# tb6612fng.net
KiCad netlist of a schematic drawn in Altium Designer
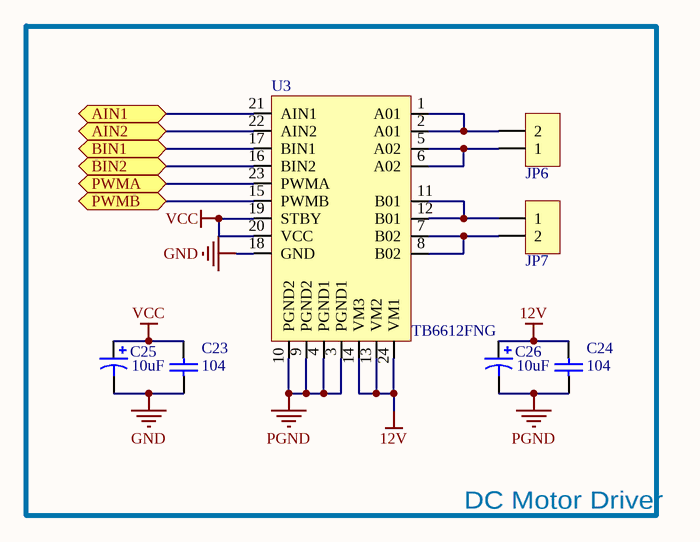
[diagram p0: tb6612fng.SchDoc]

(export (version "E")
  (design (tool "Eeschema 10.0.6"))
  (components
    (comp (ref "C23")
      (value "104")
      (footprint "C 0603_L")
      (description "Capacitor")
      (fields (field (name "PUBLISHER") "Altium Limited"))
      (libsource (lib "Miscellaneous Devices") (part "Cap"))
    )
    (comp (ref "C24")
      (value "104")
      (footprint "C 0603_L")
      (description "Capacitor")
      (fields (field (name "PUBLISHER") "Altium Limited"))
      (libsource (lib "Miscellaneous Devices") (part "Cap"))
    )
    (comp (ref "C25")
      (value "10uF")
      (footprint "CD A(3216)")
      (description "Polarized Capacitor (Radial)")
      (fields (field (name "PUBLISHER") "Altium Limited"))
      (libsource (lib "Miscellaneous Devices") (part "Cap Pol1"))
    )
    (comp (ref "C26")
      (value "10uF")
      (footprint "CD A(3216)")
      (description "Polarized Capacitor (Radial)")
      (fields (field (name "PUBLISHER") "Altium Limited"))
      (libsource (lib "Miscellaneous Devices") (part "Cap Pol1"))
    )
    (comp (ref "JP6")
      (value "HDR-1X2")
      (footprint "XH2.54-LI-2P")
      (description "2P接插件")
      (fields (field (name "版权归属") "源创客"))
      (libsource (lib "4.5   - 接插件-脚距2.54") (part "Header 2"))
    )
    (comp (ref "JP7")
      (value "HDR-1X2")
      (footprint "XH2.54-LI-2P")
      (description "2P接插件")
      (fields (field (name "版权归属") "源创客"))
      (libsource (lib "") (part "Header 2_1"))
    )
    (comp (ref "U3")
      (value "TB6612FNG")
      (footprint "SSOP24_N")
      (description "DC_MOTOR_DRIVER")
      (libsource (lib "主控板载芯片") (part "TB6612FNG"))
    )
  )
  (nets
    (net (code "1") (name "/AIN1") (class "Default")
      (node (ref "U3") (pin "21") (pinfunction "AIN1_21") (pintype "passive"))
    )
    (net (code "2") (name "/AIN2") (class "Default")
      (node (ref "U3") (pin "22") (pinfunction "AIN2_22") (pintype "passive"))
    )
    (net (code "3") (name "/BIN1") (class "Default")
      (node (ref "U3") (pin "17") (pinfunction "BIN1_17") (pintype "passive"))
    )
    (net (code "4") (name "/BIN2") (class "Default")
      (node (ref "U3") (pin "16") (pinfunction "BIN2_16") (pintype "passive"))
    )
    (net (code "5") (name "/PWMA") (class "Default")
      (node (ref "U3") (pin "23") (pinfunction "PWMA_23") (pintype "passive"))
    )
    (net (code "6") (name "/PWMB") (class "Default")
      (node (ref "U3") (pin "15") (pinfunction "PWMB_15") (pintype "passive"))
    )
    (net (code "7") (name "12V") (class "Default")
      (node (ref "C24") (pin "2") (pinfunction "2_2") (pintype "passive"))
      (node (ref "C26") (pin "1") (pinfunction "1_1") (pintype "passive"))
      (node (ref "U3") (pin "13") (pinfunction "VM2_13") (pintype "passive"))
      (node (ref "U3") (pin "14") (pinfunction "VM3_14") (pintype "passive"))
      (node (ref "U3") (pin "24") (pinfunction "VM1_24") (pintype "passive"))
    )
    (net (code "8") (name "GND") (class "Default")
      (node (ref "C23") (pin "1") (pinfunction "1_1") (pintype "passive"))
      (node (ref "C25") (pin "2") (pinfunction "2_2") (pintype "passive"))
      (node (ref "U3") (pin "18") (pinfunction "GND_18") (pintype "passive"))
    )
    (net (code "9") (name "Net-(JP6-Pad1)") (class "Default")
      (node (ref "JP6") (pin "1") (pinfunction "1_1") (pintype "passive"))
      (node (ref "U3") (pin "5") (pinfunction "A02_5") (pintype "passive"))
      (node (ref "U3") (pin "6") (pinfunction "A02_6") (pintype "passive"))
    )
    (net (code "10") (name "Net-(JP6-Pad2)") (class "Default")
      (node (ref "JP6") (pin "2") (pinfunction "2_2") (pintype "passive"))
      (node (ref "U3") (pin "1") (pinfunction "A01_1") (pintype "passive"))
      (node (ref "U3") (pin "2") (pinfunction "A01_2") (pintype "passive"))
    )
    (net (code "11") (name "Net-(JP7-Pad1)") (class "Default")
      (node (ref "JP7") (pin "1") (pinfunction "1_1") (pintype "passive"))
      (node (ref "U3") (pin "11") (pinfunction "B01_11") (pintype "passive"))
      (node (ref "U3") (pin "12") (pinfunction "B01_12") (pintype "passive"))
    )
    (net (code "12") (name "Net-(JP7-Pad2)") (class "Default")
      (node (ref "JP7") (pin "2") (pinfunction "2_2") (pintype "passive"))
      (node (ref "U3") (pin "7") (pinfunction "B02_7") (pintype "passive"))
      (node (ref "U3") (pin "8") (pinfunction "B02_8") (pintype "passive"))
    )
    (net (code "13") (name "PGND") (class "Default")
      (node (ref "C24") (pin "1") (pinfunction "1_1") (pintype "passive"))
      (node (ref "C26") (pin "2") (pinfunction "2_2") (pintype "passive"))
      (node (ref "U3") (pin "10") (pinfunction "PGND2_10") (pintype "passive"))
      (node (ref "U3") (pin "3") (pinfunction "PGND1_3") (pintype "passive"))
      (node (ref "U3") (pin "4") (pinfunction "PGND1_4") (pintype "passive"))
      (node (ref "U3") (pin "9") (pinfunction "PGND2_9") (pintype "passive"))
    )
    (net (code "14") (name "VCC") (class "Default")
      (node (ref "C23") (pin "2") (pinfunction "2_2") (pintype "passive"))
      (node (ref "C25") (pin "1") (pinfunction "1_1") (pintype "passive"))
      (node (ref "U3") (pin "19") (pinfunction "STBY_19") (pintype "passive"))
      (node (ref "U3") (pin "20") (pinfunction "VCC_20") (pintype "passive"))
    )
  )
)
